# M248B.net
KiCad netlist of a schematic drawn in EAGLE
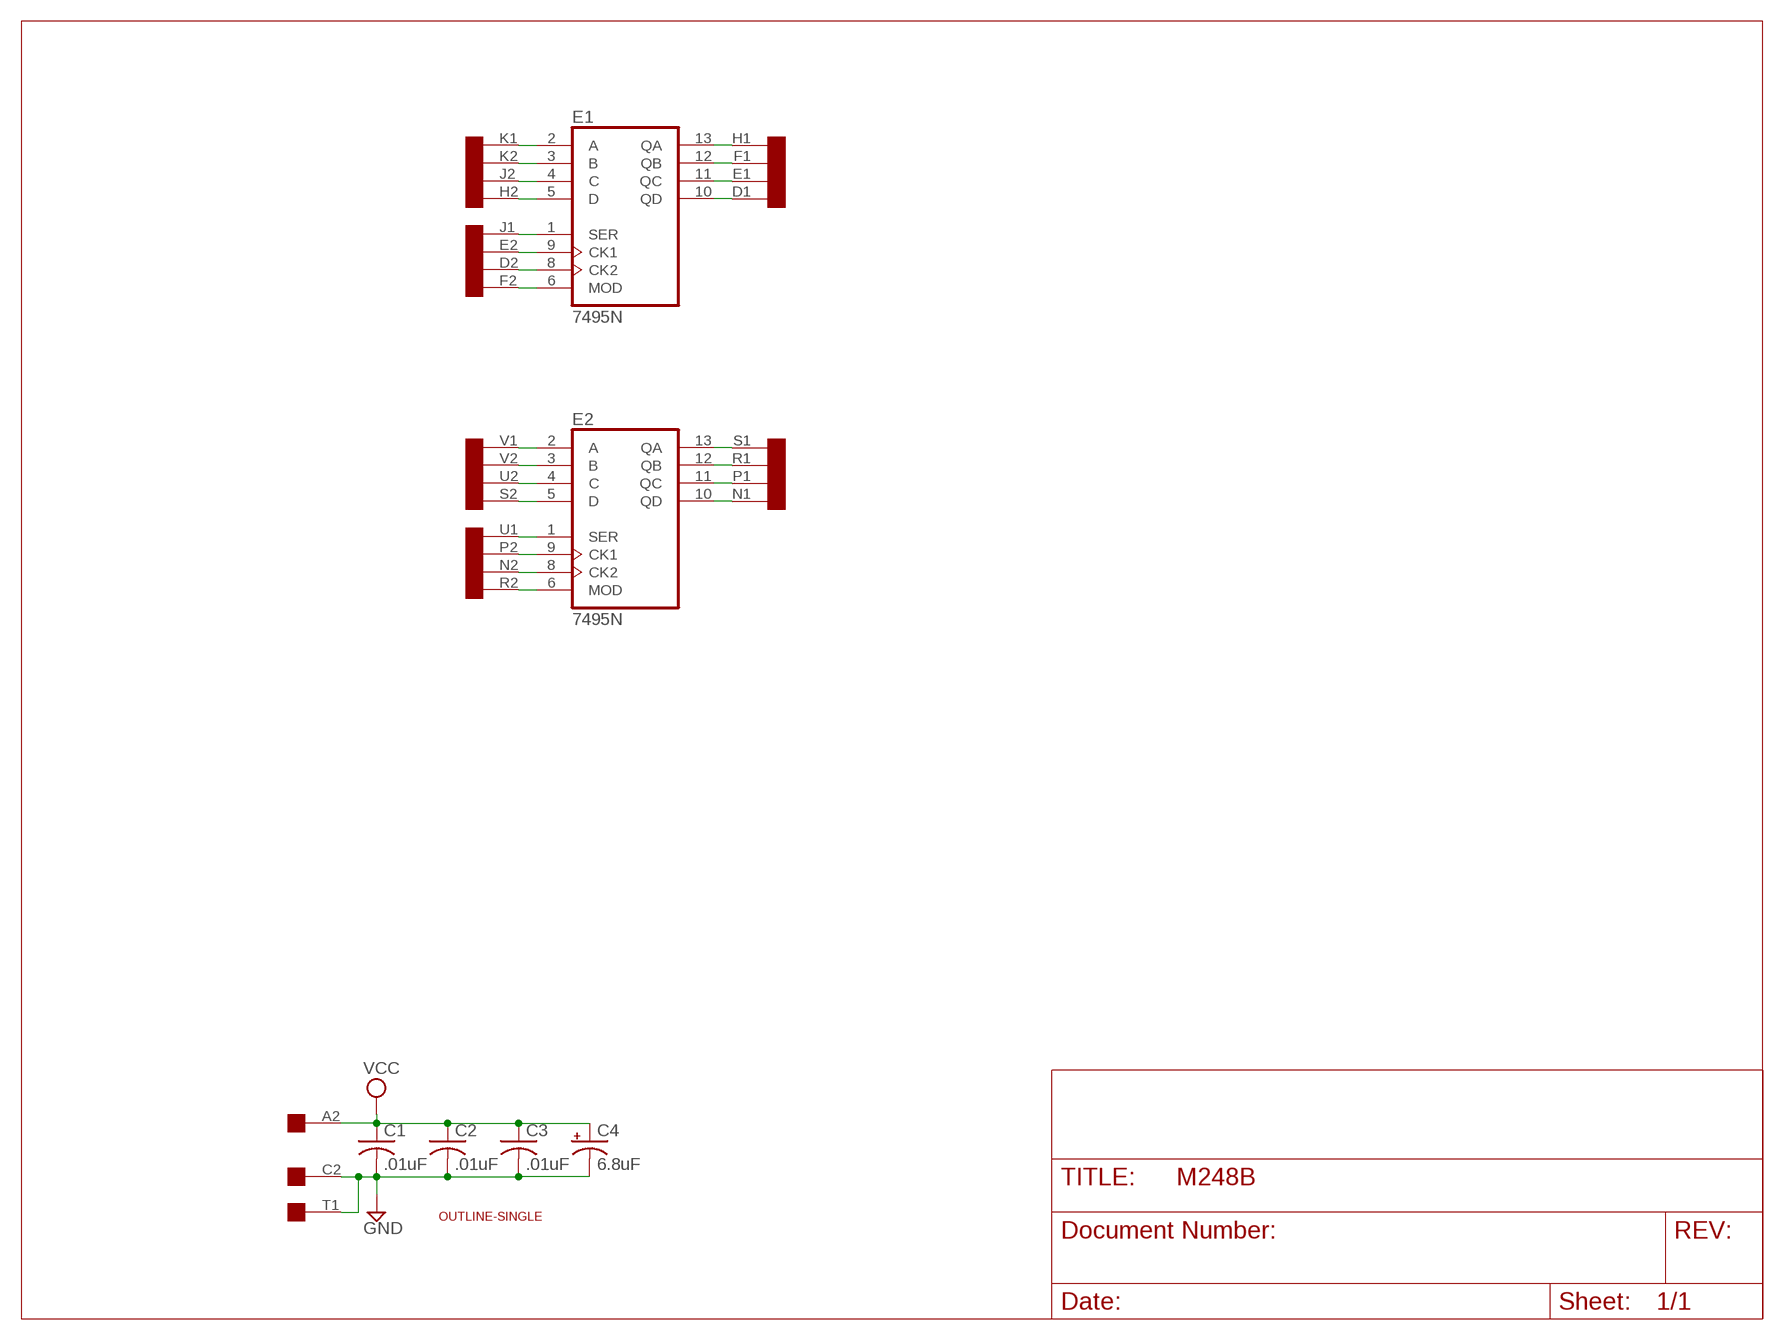
[diagram p0: schematic, sheet 1]

(export (version "E")
  (design (tool "Eeschema 10.0.6"))
  (components
    (comp (ref "C1")
      (value ".01uF")
      (footprint "eagle-import:C050-025X075")
      (libsource (lib "eagle-import") (part "C-US050-025X075"))
    )
    (comp (ref "C2")
      (value ".01uF")
      (footprint "eagle-import:C050-025X075")
      (libsource (lib "eagle-import") (part "C-US050-025X075"))
    )
    (comp (ref "C3")
      (value ".01uF")
      (footprint "eagle-import:C050-025X075")
      (libsource (lib "eagle-import") (part "C-US050-025X075"))
    )
    (comp (ref "C4")
      (value "6.8uF")
      (footprint "eagle-import:E12-8")
      (libsource (lib "eagle-import") (part "CPOL-USE20-8AXIAL"))
    )
    (comp (ref "E1")
      (value "7495N")
      (footprint "eagle-import:DIL14")
      (libsource (lib "eagle-import") (part "7495N"))
    )
    (comp (ref "E2")
      (value "7495N")
      (footprint "eagle-import:DIL14")
      (libsource (lib "eagle-import") (part "7495N"))
    )
    (comp (ref "U$1")
      (value "OUTLINE-SINGLE")
      (footprint "eagle-import:SINGLE")
      (libsource (lib "eagle-import") (part "OUTLINE-SINGLE"))
    )
    (comp (ref "U$2")
      (value "SINGLE")
      (footprint "eagle-import:EDGE-CON2")
      (libsource (lib "eagle-import") (part "SINGLE"))
    )
  )
  (nets
    (net (code "1") (name "GND") (class "Default")
      (node (ref "C1") (pin "2") (pinfunction "2_2") (pintype "passive"))
      (node (ref "C2") (pin "2") (pinfunction "2_2") (pintype "passive"))
      (node (ref "C3") (pin "2") (pinfunction "2_2") (pintype "passive"))
      (node (ref "C4") (pin "-") (pinfunction "-_-") (pintype "passive"))
      (node (ref "U$2") (pin "C2") (pinfunction "1_C2") (pintype "bidirectional"))
      (node (ref "U$2") (pin "T1") (pinfunction "1_T1") (pintype "bidirectional"))
    )
    (net (code "2") (name "Net-(E1A-A)") (class "Default")
      (node (ref "E1") (pin "2") (pinfunction "A_2") (pintype "input"))
      (node (ref "U$2") (pin "K1") (pinfunction "1_K1") (pintype "bidirectional"))
    )
    (net (code "3") (name "Net-(E1A-B)") (class "Default")
      (node (ref "E1") (pin "3") (pinfunction "B_3") (pintype "input"))
      (node (ref "U$2") (pin "K2") (pinfunction "1_K2") (pintype "bidirectional"))
    )
    (net (code "4") (name "Net-(E1A-C)") (class "Default")
      (node (ref "E1") (pin "4") (pinfunction "C_4") (pintype "input"))
      (node (ref "U$2") (pin "J2") (pinfunction "1_J2") (pintype "bidirectional"))
    )
    (net (code "5") (name "Net-(E1A-CK1)") (class "Default")
      (node (ref "E1") (pin "9") (pinfunction "CK1_9") (pintype "input"))
      (node (ref "U$2") (pin "E2") (pinfunction "1_E2") (pintype "bidirectional"))
    )
    (net (code "6") (name "Net-(E1A-CK2)") (class "Default")
      (node (ref "E1") (pin "8") (pinfunction "CK2_8") (pintype "input"))
      (node (ref "U$2") (pin "D2") (pinfunction "1_D2") (pintype "bidirectional"))
    )
    (net (code "7") (name "Net-(E1A-D)") (class "Default")
      (node (ref "E1") (pin "5") (pinfunction "D_5") (pintype "input"))
      (node (ref "U$2") (pin "H2") (pinfunction "1_H2") (pintype "bidirectional"))
    )
    (net (code "8") (name "Net-(E1A-MOD)") (class "Default")
      (node (ref "E1") (pin "6") (pinfunction "MOD_6") (pintype "input"))
      (node (ref "U$2") (pin "F2") (pinfunction "1_F2") (pintype "bidirectional"))
    )
    (net (code "9") (name "Net-(E1A-QA)") (class "Default")
      (node (ref "E1") (pin "13") (pinfunction "QA_13") (pintype "output"))
      (node (ref "U$2") (pin "H1") (pinfunction "1_H1") (pintype "bidirectional"))
    )
    (net (code "10") (name "Net-(E1A-QB)") (class "Default")
      (node (ref "E1") (pin "12") (pinfunction "QB_12") (pintype "output"))
      (node (ref "U$2") (pin "F1") (pinfunction "1_F1") (pintype "bidirectional"))
    )
    (net (code "11") (name "Net-(E1A-QC)") (class "Default")
      (node (ref "E1") (pin "11") (pinfunction "QC_11") (pintype "output"))
      (node (ref "U$2") (pin "E1") (pinfunction "1_E1") (pintype "bidirectional"))
    )
    (net (code "12") (name "Net-(E1A-QD)") (class "Default")
      (node (ref "E1") (pin "10") (pinfunction "QD_10") (pintype "output"))
      (node (ref "U$2") (pin "D1") (pinfunction "1_D1") (pintype "bidirectional"))
    )
    (net (code "13") (name "Net-(E1A-SER)") (class "Default")
      (node (ref "E1") (pin "1") (pinfunction "SER_1") (pintype "input"))
      (node (ref "U$2") (pin "J1") (pinfunction "1_J1") (pintype "bidirectional"))
    )
    (net (code "14") (name "Net-(E2A-A)") (class "Default")
      (node (ref "E2") (pin "2") (pinfunction "A_2") (pintype "input"))
      (node (ref "U$2") (pin "V1") (pinfunction "1_V1") (pintype "bidirectional"))
    )
    (net (code "15") (name "Net-(E2A-B)") (class "Default")
      (node (ref "E2") (pin "3") (pinfunction "B_3") (pintype "input"))
      (node (ref "U$2") (pin "V2") (pinfunction "1_V2") (pintype "bidirectional"))
    )
    (net (code "16") (name "Net-(E2A-C)") (class "Default")
      (node (ref "E2") (pin "4") (pinfunction "C_4") (pintype "input"))
      (node (ref "U$2") (pin "U2") (pinfunction "1_U2") (pintype "bidirectional"))
    )
    (net (code "17") (name "Net-(E2A-CK1)") (class "Default")
      (node (ref "E2") (pin "9") (pinfunction "CK1_9") (pintype "input"))
      (node (ref "U$2") (pin "P2") (pinfunction "1_P2") (pintype "bidirectional"))
    )
    (net (code "18") (name "Net-(E2A-CK2)") (class "Default")
      (node (ref "E2") (pin "8") (pinfunction "CK2_8") (pintype "input"))
      (node (ref "U$2") (pin "N2") (pinfunction "1_N2") (pintype "bidirectional"))
    )
    (net (code "19") (name "Net-(E2A-D)") (class "Default")
      (node (ref "E2") (pin "5") (pinfunction "D_5") (pintype "input"))
      (node (ref "U$2") (pin "S2") (pinfunction "1_S2") (pintype "bidirectional"))
    )
    (net (code "20") (name "Net-(E2A-MOD)") (class "Default")
      (node (ref "E2") (pin "6") (pinfunction "MOD_6") (pintype "input"))
      (node (ref "U$2") (pin "R2") (pinfunction "1_R2") (pintype "bidirectional"))
    )
    (net (code "21") (name "Net-(E2A-QA)") (class "Default")
      (node (ref "E2") (pin "13") (pinfunction "QA_13") (pintype "output"))
      (node (ref "U$2") (pin "S1") (pinfunction "1_S1") (pintype "bidirectional"))
    )
    (net (code "22") (name "Net-(E2A-QB)") (class "Default")
      (node (ref "E2") (pin "12") (pinfunction "QB_12") (pintype "output"))
      (node (ref "U$2") (pin "R1") (pinfunction "1_R1") (pintype "bidirectional"))
    )
    (net (code "23") (name "Net-(E2A-QC)") (class "Default")
      (node (ref "E2") (pin "11") (pinfunction "QC_11") (pintype "output"))
      (node (ref "U$2") (pin "P1") (pinfunction "1_P1") (pintype "bidirectional"))
    )
    (net (code "24") (name "Net-(E2A-QD)") (class "Default")
      (node (ref "E2") (pin "10") (pinfunction "QD_10") (pintype "output"))
      (node (ref "U$2") (pin "N1") (pinfunction "1_N1") (pintype "bidirectional"))
    )
    (net (code "25") (name "Net-(E2A-SER)") (class "Default")
      (node (ref "E2") (pin "1") (pinfunction "SER_1") (pintype "input"))
      (node (ref "U$2") (pin "U1") (pinfunction "1_U1") (pintype "bidirectional"))
    )
    (net (code "26") (name "VCC") (class "Default")
      (node (ref "C1") (pin "1") (pinfunction "1_1") (pintype "passive"))
      (node (ref "C2") (pin "1") (pinfunction "1_1") (pintype "passive"))
      (node (ref "C3") (pin "1") (pinfunction "1_1") (pintype "passive"))
      (node (ref "C4") (pin "+") (pinfunction "+_+") (pintype "passive"))
      (node (ref "U$2") (pin "A2") (pinfunction "1_A2") (pintype "bidirectional"))
    )
  )
)
